# schematic.net
KiCad netlist of a schematic drawn in Altium Designer
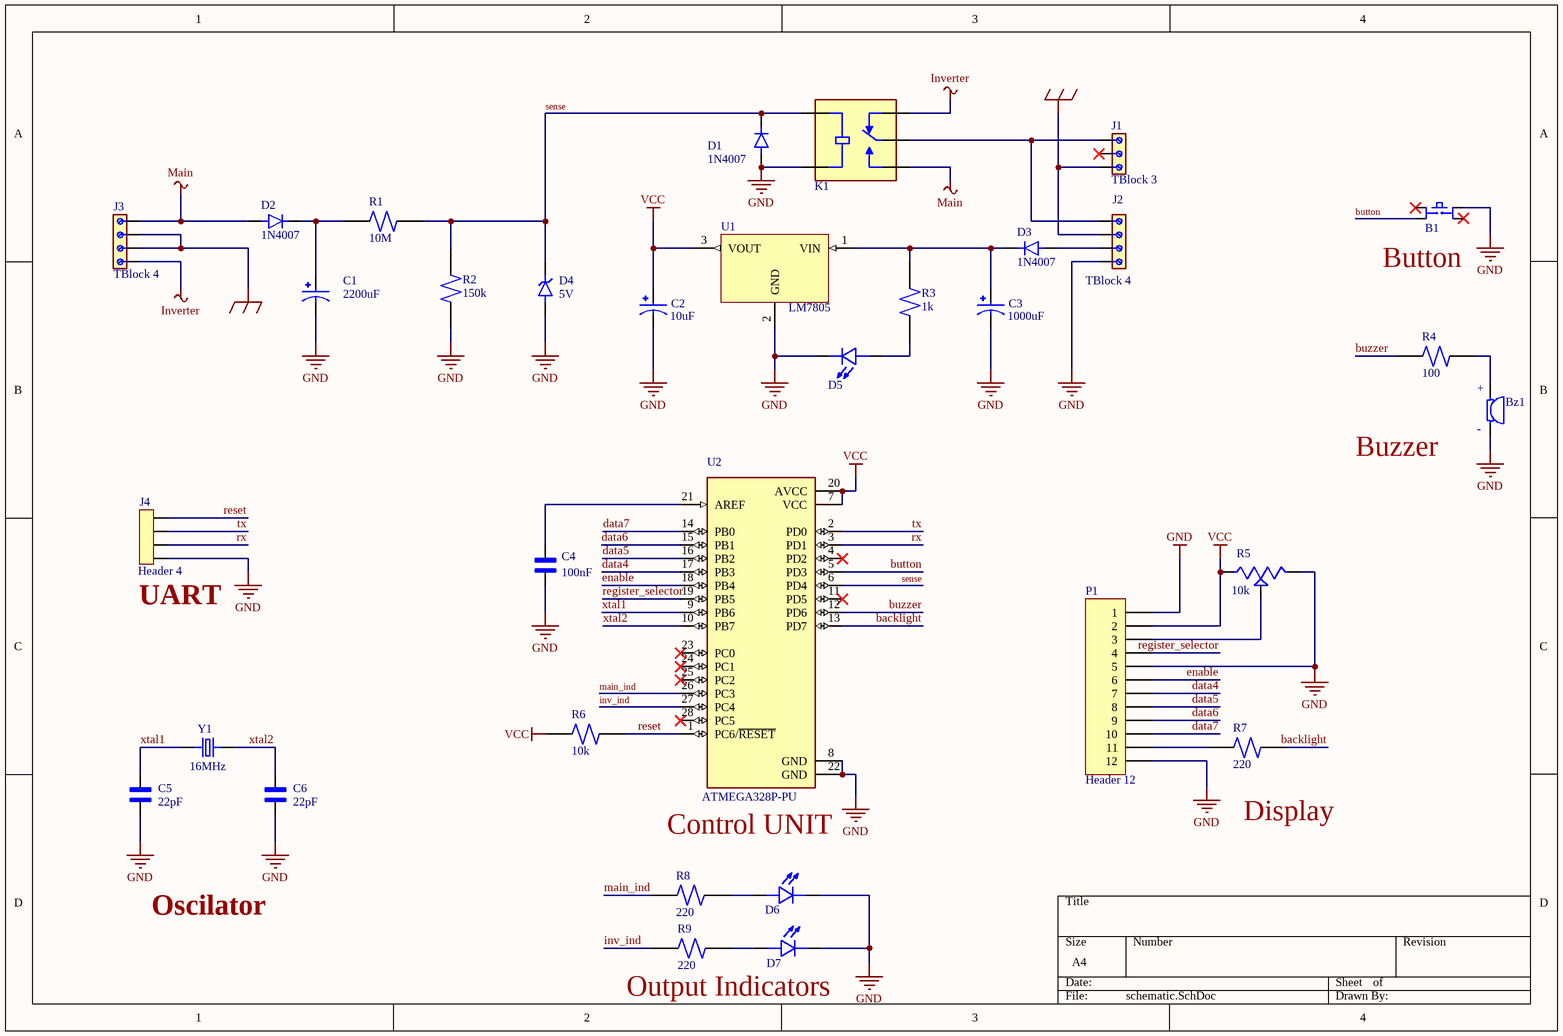
[diagram p0: schematic.SchDoc]

(export (version "E")
  (design (tool "Eeschema 10.0.6"))
  (components
    (comp (ref "B1")
      (value "Push button")
      (footprint "SW_TS02-66-95-BK-260-LCR-D")
      (libsource (lib "Installed library") (part "Push button"))
    )
    (comp (ref "Bz1")
      (value "AI-1223-TWT-12V-R")
      (footprint "XDCR_AI-1223-TWT-12V-R")
      (description "ELECTRO-MECHANICAL AUDIO INDICATOR")
      (fields (field (name "MF") "PUI Audio,"))
      (libsource (lib "Installed library") (part "Buzzer"))
    )
    (comp (ref "C1")
      (value "2200uF")
      (footprint "CAPPRD750W80D1600H2500")
      (fields (field (name "MF") "Panasonic") (field (name "MP") "ECA2GM330"))
      (libsource (lib "Installed library") (part "Capacitor (16 x 25mm)"))
    )
    (comp (ref "C2")
      (value "10uF")
      (footprint "CAPPRD500W50D500H1100")
      (description "FS-A")
      (fields (field (name "MF") "{'manufacturer': u'Panasonic'}") (field (name "MP") "EEUFS0J221B"))
      (libsource (lib "Installed library") (part "Electrolytic capacitor"))
    )
    (comp (ref "C3")
      (value "1000uF")
      (footprint "CAPPRD500W50D500H1100")
      (description "FS-A")
      (fields (field (name "MF") "{'manufacturer': u'Panasonic'}") (field (name "MP") "EEUFS0J221B"))
      (libsource (lib "Installed library") (part "Electrolytic capacitor"))
    )
    (comp (ref "C4")
      (value "100nF")
      (footprint "CAPRB500W50L450T300H550")
      (description "2200 pF Â±10% 250V Ceramic Capacitor X7R Radial")
      (fields (field (name "DIGI-KEY_PART_NUMBER") "445-173386-1-ND") (field (name "MF") "TDK"))
      (libsource (lib "Installed library") (part "Ceramic capacitor"))
    )
    (comp (ref "C5")
      (value "22pF")
      (footprint "CAPRB500W50L450T300H550")
      (description "2200 pF Â±10% 250V Ceramic Capacitor X7R Radial")
      (fields (field (name "DIGI-KEY_PART_NUMBER") "445-173386-1-ND") (field (name "MF") "TDK"))
      (libsource (lib "Installed library") (part "Ceramic capacitor"))
    )
    (comp (ref "C6")
      (value "22pF")
      (footprint "CAPRB500W50L450T300H550")
      (description "2200 pF Â±10% 250V Ceramic Capacitor X7R Radial")
      (fields (field (name "DIGI-KEY_PART_NUMBER") "445-173386-1-ND") (field (name "MF") "TDK"))
      (libsource (lib "Installed library") (part "Ceramic capacitor"))
    )
    (comp (ref "D1")
      (value "1N4007")
      (footprint "DIOAD1060W80L520D270")
      (description "Diode Switching 1KV 1A 2-Pin DO-41")
      (libsource (lib "Components") (part "1N4007"))
    )
    (comp (ref "D2")
      (value "1N4007")
      (footprint "DIOAD1060W80L520D270")
      (description "Diode Switching 1KV 1A 2-Pin DO-41")
      (libsource (lib "Components") (part "1N4007"))
    )
    (comp (ref "D3")
      (value "1N4007")
      (footprint "DIOAD1060W80L520D270")
      (description "Diode Switching 1KV 1A 2-Pin DO-41")
      (libsource (lib "Components") (part "1N4007"))
    )
    (comp (ref "D4")
      (value "5V")
      (footprint "DIOAD1060W70L435D230")
      (description "Zener Diode 16V 1W Â±5% Through Hole DO-204AL (DO-41)")
      (fields (field (name "MP") "1N4745A") (field (name "MF") "ON Semiconductor"))
      (libsource (lib "Installed library") (part "Zenner diode"))
    )
    (comp (ref "D5")
      (value "L08R5000Q1")
      (footprint "LEDRD254W57D500H1070")
      (description "LED, Orange, Through Hole, T-1 3/4 (5mm), 30 mA, 2.1 V, 635 nm")
      (fields (field (name "MF") "{'manufacturer': u'LED Technology'}"))
      (libsource (lib "Installed library") (part "LED"))
    )
    (comp (ref "D6")
      (value "L08R5000Q1")
      (footprint "LEDRD254W57D500H1070")
      (description "LED, Orange, Through Hole, T-1 3/4 (5mm), 30 mA, 2.1 V, 635 nm")
      (fields (field (name "MF") "{'manufacturer': u'LED Technology'}"))
      (libsource (lib "Installed library") (part "LED"))
    )
    (comp (ref "D7")
      (value "L08R5000Q1")
      (footprint "LEDRD254W57D500H1070")
      (description "LED, Orange, Through Hole, T-1 3/4 (5mm), 30 mA, 2.1 V, 635 nm")
      (fields (field (name "MF") "{'manufacturer': u'LED Technology'}"))
      (libsource (lib "Installed library") (part "LED"))
    )
    (comp (ref "J1")
      (value "TBlock 3")
      (footprint "Terminal block - 3Pins")
      (description "5.08 MM TERMINAL BLOCK;")
      (fields (field (name "MP") "691216510003S") (field (name "MF") "Wurth Electronics"))
      (libsource (lib "Installed library") (part "3Pins Terminal block"))
    )
    (comp (ref "J2")
      (value "TBlock 4")
      (footprint "691241510004")
      (fields (field (name "MP") "691241510004") (field (name "MF") "WÃ¼rth Elektronik"))
      (libsource (lib "Installed library") (part "Terminal block - 4Pins"))
    )
    (comp (ref "J3")
      (value "TBlock 4")
      (footprint "691241510004")
      (fields (field (name "MP") "691241510004") (field (name "MF") "WÃ¼rth Elektronik"))
      (libsource (lib "") (part "Terminal block - 4Pins_1"))
    )
    (comp (ref "J4")
      (value "Header 4")
      (footprint "SULLINS_PPTC041LFBN-RC")
      (description "4 Position Header Connector Through Hole")
      (fields (field (name "MP") "PPTC041LFBN-RC") (field (name "MF") "Sullins Connector"))
      (libsource (lib "Installed library") (part "Female header - 4Pins"))
    )
    (comp (ref "K1")
      (value "JQC-3F-1C-24VDC")
      (footprint "RELAY_JQC-3F-1C-24VDC")
      (description "Miniature PCB Relay 24VDC, 10A 250VAC, 15A 125VAC, 10A 250VAC")
      (libsource (lib "Installed library") (part "Relay (Standard)"))
    )
    (comp (ref "P1")
      (value "Header 12")
      (footprint "HDR1X12")
      (description "Header, 12-Pin")
      (fields (field (name "PUBLISHER") "Altium Limited"))
      (libsource (lib "Miscellaneous Connectors") (part "Header 12"))
    )
    (comp (ref "R1")
      (value "10M")
      (footprint "RESAD1100W55L680D260")
      (description "(MFR-25FBF52-10K) 10,2 kOhm bei 1% 0,25W, 1/4W Durchbohrlochwiderstand Axial Metal Film")
      (fields (field (name "DIGI-KEY_PART_NUMBER") "10.2KXBK-ND") (field (name "MF") "Yageo"))
      (libsource (lib "Installed library") (part "Resistor (0.25W)"))
    )
    (comp (ref "R2")
      (value "150k")
      (footprint "RESAD1100W55L680D260")
      (description "(MFR-25FBF52-10K) 10,2 kOhm bei 1% 0,25W, 1/4W Durchbohrlochwiderstand Axial Metal Film")
      (fields (field (name "DIGI-KEY_PART_NUMBER") "10.2KXBK-ND") (field (name "MF") "Yageo"))
      (libsource (lib "Installed library") (part "Resistor (0.25W)"))
    )
    (comp (ref "R3")
      (value "1k")
      (footprint "RESAD1100W55L680D260")
      (description "(MFR-25FBF52-10K) 10,2 kOhm bei 1% 0,25W, 1/4W Durchbohrlochwiderstand Axial Metal Film")
      (fields (field (name "DIGI-KEY_PART_NUMBER") "10.2KXBK-ND") (field (name "MF") "Yageo"))
      (libsource (lib "Installed library") (part "Resistor (0.25W)"))
    )
    (comp (ref "R4")
      (value "100")
      (footprint "RESAD1100W55L680D260")
      (description "(MFR-25FBF52-10K) 10,2 kOhm bei 1% 0,25W, 1/4W Durchbohrlochwiderstand Axial Metal Film")
      (fields (field (name "DIGI-KEY_PART_NUMBER") "10.2KXBK-ND") (field (name "MF") "Yageo"))
      (libsource (lib "Installed library") (part "Resistor (0.25W)"))
    )
    (comp (ref "R5")
      (value "10k")
      (footprint "TRIM_3306F-1-105")
      (fields (field (name "MF") "Bourns") (field (name "MP") "3306F-1-105"))
      (libsource (lib "Installed library") (part "Potentiometer1"))
    )
    (comp (ref "R6")
      (value "10k")
      (footprint "RESAD1100W55L680D260")
      (description "(MFR-25FBF52-10K) 10,2 kOhm bei 1% 0,25W, 1/4W Durchbohrlochwiderstand Axial Metal Film")
      (fields (field (name "DIGI-KEY_PART_NUMBER") "10.2KXBK-ND") (field (name "MF") "Yageo"))
      (libsource (lib "Installed library") (part "Resistor (0.25W)"))
    )
    (comp (ref "R7")
      (value "220")
      (footprint "RESAD1100W55L680D260")
      (description "(MFR-25FBF52-10K) 10,2 kOhm bei 1% 0,25W, 1/4W Durchbohrlochwiderstand Axial Metal Film")
      (fields (field (name "DIGI-KEY_PART_NUMBER") "10.2KXBK-ND") (field (name "MF") "Yageo"))
      (libsource (lib "Installed library") (part "Resistor (0.25W)"))
    )
    (comp (ref "R8")
      (value "220")
      (footprint "RESAD1100W55L680D260")
      (description "(MFR-25FBF52-10K) 10,2 kOhm bei 1% 0,25W, 1/4W Durchbohrlochwiderstand Axial Metal Film")
      (fields (field (name "DIGI-KEY_PART_NUMBER") "10.2KXBK-ND") (field (name "MF") "Yageo"))
      (libsource (lib "Installed library") (part "Resistor (0.25W)"))
    )
    (comp (ref "R9")
      (value "220")
      (footprint "RESAD1100W55L680D260")
      (description "(MFR-25FBF52-10K) 10,2 kOhm bei 1% 0,25W, 1/4W Durchbohrlochwiderstand Axial Metal Film")
      (fields (field (name "DIGI-KEY_PART_NUMBER") "10.2KXBK-ND") (field (name "MF") "Yageo"))
      (libsource (lib "Installed library") (part "Resistor (0.25W)"))
    )
    (comp (ref "U1")
      (value "LM7805")
      (footprint "TO255P1020X450X1968-3")
      (fields (field (name "MP") "LM7805CT/NOPB"))
      (libsource (lib "Voltage regulator") (part "LM78__"))
    )
    (comp (ref "U2")
      (value "ATMEGA328P-PU")
      (footprint "DIP794W46P254L2967H457Q28B")
      (description "ATmega Series 20 MHz 32 KB Flash 2 KB SRAM 8-Bit Microcontroller - DIP-28")
      (libsource (lib "Installed library") (part "ATMEGA328P-PU"))
    )
    (comp (ref "Y1")
      (value "16MHz")
      (footprint "XTAL_ECS-160-20-4X")
      (description "CRYSTAL T/H")
      (fields (field (name "MF") "{'manufacturer': u'ECS Inc.'}") (field (name "MP") "ECS-160-S-4"))
      (libsource (lib "Installed library") (part "Crystal oscilator"))
    )
  )
  (nets
    (net (code "1") (name "/backlight") (class "Default")
      (node (ref "R7") (pin "2") (pinfunction "2_2") (pintype "passive"))
      (node (ref "U2") (pin "13") (pinfunction "PD7_13") (pintype "bidirectional"))
    )
    (net (code "2") (name "/button") (class "Default")
      (node (ref "B1") (pin "2") (pinfunction "2_2") (pintype "passive"))
      (node (ref "U2") (pin "5") (pinfunction "PD3_5") (pintype "bidirectional"))
    )
    (net (code "3") (name "/buzzer") (class "Default")
      (node (ref "R4") (pin "1") (pinfunction "1_1") (pintype "passive"))
      (node (ref "U2") (pin "12") (pinfunction "PD6_12") (pintype "bidirectional"))
    )
    (net (code "4") (name "/data4") (class "Default")
      (node (ref "P1") (pin "7") (pinfunction "7_7") (pintype "passive"))
      (node (ref "U2") (pin "17") (pinfunction "PB3_17") (pintype "bidirectional"))
    )
    (net (code "5") (name "/data5") (class "Default")
      (node (ref "P1") (pin "8") (pinfunction "8_8") (pintype "passive"))
      (node (ref "U2") (pin "16") (pinfunction "PB2_16") (pintype "bidirectional"))
    )
    (net (code "6") (name "/data6") (class "Default")
      (node (ref "P1") (pin "9") (pinfunction "9_9") (pintype "passive"))
      (node (ref "U2") (pin "15") (pinfunction "PB1_15") (pintype "bidirectional"))
    )
    (net (code "7") (name "/data7") (class "Default")
      (node (ref "P1") (pin "10") (pinfunction "10_10") (pintype "passive"))
      (node (ref "U2") (pin "14") (pinfunction "PB0_14") (pintype "bidirectional"))
    )
    (net (code "8") (name "/enable") (class "Default")
      (node (ref "P1") (pin "6") (pinfunction "6_6") (pintype "passive"))
      (node (ref "U2") (pin "18") (pinfunction "PB4_18") (pintype "bidirectional"))
    )
    (net (code "9") (name "/inv_ind") (class "Default")
      (node (ref "R9") (pin "2") (pinfunction "2_2") (pintype "passive"))
      (node (ref "U2") (pin "27") (pinfunction "PC4_27") (pintype "bidirectional"))
    )
    (net (code "10") (name "/main_ind") (class "Default")
      (node (ref "R8") (pin "2") (pinfunction "2_2") (pintype "passive"))
      (node (ref "U2") (pin "26") (pinfunction "PC3_26") (pintype "bidirectional"))
    )
    (net (code "11") (name "/register_selector") (class "Default")
      (node (ref "P1") (pin "4") (pinfunction "4_4") (pintype "passive"))
      (node (ref "U2") (pin "19") (pinfunction "PB5_19") (pintype "bidirectional"))
    )
    (net (code "12") (name "/reset") (class "Default")
      (node (ref "J4") (pin "1") (pinfunction "1_1") (pintype "passive"))
      (node (ref "R6") (pin "1") (pinfunction "1_1") (pintype "passive"))
      (node (ref "U2") (pin "1") (pinfunction "PC6/~{RESET}_1") (pintype "bidirectional"))
    )
    (net (code "13") (name "/rx") (class "Default")
      (node (ref "J4") (pin "3") (pinfunction "3_3") (pintype "passive"))
      (node (ref "U2") (pin "3") (pinfunction "PD1_3") (pintype "bidirectional"))
    )
    (net (code "14") (name "/sense") (class "Default")
      (node (ref "D1") (pin "C") (pinfunction "C_C") (pintype "passive"))
      (node (ref "D4") (pin "C") (pinfunction "K_C") (pintype "passive"))
      (node (ref "K1") (pin "COIL1") (pinfunction "COIL1_COIL1") (pintype "passive"))
      (node (ref "R1") (pin "1") (pinfunction "1_1") (pintype "passive"))
      (node (ref "R2") (pin "1") (pinfunction "1_1") (pintype "passive"))
      (node (ref "U2") (pin "6") (pinfunction "PD4_6") (pintype "bidirectional"))
    )
    (net (code "15") (name "/tx") (class "Default")
      (node (ref "J4") (pin "2") (pinfunction "2_2") (pintype "passive"))
      (node (ref "U2") (pin "2") (pinfunction "PD0_2") (pintype "bidirectional"))
    )
    (net (code "16") (name "/xtal1") (class "Default")
      (node (ref "C5") (pin "2") (pinfunction "2_2") (pintype "passive"))
      (node (ref "U2") (pin "9") (pinfunction "PB6_9") (pintype "bidirectional"))
      (node (ref "Y1") (pin "2") (pinfunction "2_2") (pintype "passive"))
    )
    (net (code "17") (name "/xtal2") (class "Default")
      (node (ref "C6") (pin "2") (pinfunction "2_2") (pintype "passive"))
      (node (ref "U2") (pin "10") (pinfunction "PB7_10") (pintype "bidirectional"))
      (node (ref "Y1") (pin "1") (pinfunction "1_1") (pintype "passive"))
    )
    (net (code "18") (name "AGND") (class "Default")
      (node (ref "J1") (pin "3") (pinfunction "3_3") (pintype "passive"))
      (node (ref "J2") (pin "2") (pinfunction "2_2") (pintype "passive"))
      (node (ref "J3") (pin "2") (pinfunction "2_2") (pintype "passive"))
      (node (ref "J3") (pin "3") (pinfunction "3_3") (pintype "passive"))
    )
    (net (code "19") (name "GND") (class "Default")
      (node (ref "B1") (pin "3") (pinfunction "3_3") (pintype "passive"))
      (node (ref "Bz1") (pin "N") (pinfunction "NEG_N") (pintype "passive"))
      (node (ref "C1") (pin "N") (pinfunction "N_N") (pintype "passive"))
      (node (ref "C2") (pin "N") (pinfunction "N_N") (pintype "passive"))
      (node (ref "C3") (pin "N") (pinfunction "N_N") (pintype "passive"))
      (node (ref "C4") (pin "1") (pinfunction "1_1") (pintype "passive"))
      (node (ref "C5") (pin "1") (pinfunction "1_1") (pintype "passive"))
      (node (ref "C6") (pin "1") (pinfunction "1_1") (pintype "passive"))
      (node (ref "D1") (pin "A") (pinfunction "A_A") (pintype "passive"))
      (node (ref "D4") (pin "A") (pinfunction "A_A") (pintype "passive"))
      (node (ref "D5") (pin "C") (pinfunction "C_C") (pintype "passive"))
      (node (ref "D6") (pin "C") (pinfunction "C_C") (pintype "passive"))
      (node (ref "D7") (pin "C") (pinfunction "C_C") (pintype "passive"))
      (node (ref "J2") (pin "4") (pinfunction "4_4") (pintype "passive"))
      (node (ref "J4") (pin "4") (pinfunction "4_4") (pintype "passive"))
      (node (ref "K1") (pin "COIL2") (pinfunction "COIL2_COIL2") (pintype "passive"))
      (node (ref "P1") (pin "1") (pinfunction "1_1") (pintype "passive"))
      (node (ref "P1") (pin "12") (pinfunction "12_12") (pintype "passive"))
      (node (ref "P1") (pin "5") (pinfunction "5_5") (pintype "passive"))
      (node (ref "R2") (pin "2") (pinfunction "2_2") (pintype "passive"))
      (node (ref "R5") (pin "3") (pinfunction "CW_3") (pintype "passive"))
      (node (ref "U1") (pin "2") (pinfunction "GND_2") (pintype "passive"))
      (node (ref "U2") (pin "22") (pinfunction "GND_22") (pintype "power_in"))
      (node (ref "U2") (pin "8") (pinfunction "GND_8") (pintype "power_in"))
    )
    (net (code "20") (name "Inverter") (class "Default")
      (node (ref "J3") (pin "4") (pinfunction "4_4") (pintype "passive"))
      (node (ref "K1") (pin "NC") (pinfunction "NC_NC") (pintype "passive"))
    )
    (net (code "21") (name "Main") (class "Default")
      (node (ref "D2") (pin "A") (pinfunction "A_A") (pintype "passive"))
      (node (ref "J3") (pin "1") (pinfunction "1_1") (pintype "passive"))
      (node (ref "K1") (pin "NO") (pinfunction "NO_NO") (pintype "passive"))
    )
    (net (code "22") (name "Net-(Bz1-POS)") (class "Default")
      (node (ref "Bz1") (pin "P") (pinfunction "POS_P") (pintype "passive"))
      (node (ref "R4") (pin "2") (pinfunction "2_2") (pintype "passive"))
    )
    (net (code "23") (name "Net-(C1-PadP)") (class "Default")
      (node (ref "C1") (pin "P") (pinfunction "P_P") (pintype "passive"))
      (node (ref "D2") (pin "C") (pinfunction "C_C") (pintype "passive"))
      (node (ref "R1") (pin "2") (pinfunction "2_2") (pintype "passive"))
    )
    (net (code "24") (name "Net-(D3-PadA)") (class "Default")
      (node (ref "D3") (pin "A") (pinfunction "A_A") (pintype "passive"))
      (node (ref "J2") (pin "3") (pinfunction "3_3") (pintype "passive"))
    )
    (net (code "25") (name "Net-(D5-PadA)") (class "Default")
      (node (ref "D5") (pin "A") (pinfunction "A_A") (pintype "passive"))
      (node (ref "R3") (pin "1") (pinfunction "1_1") (pintype "passive"))
    )
    (net (code "26") (name "Net-(D6-PadA)") (class "Default")
      (node (ref "D6") (pin "A") (pinfunction "A_A") (pintype "passive"))
      (node (ref "R8") (pin "1") (pinfunction "1_1") (pintype "passive"))
    )
    (net (code "27") (name "Net-(D7-PadA)") (class "Default")
      (node (ref "D7") (pin "A") (pinfunction "A_A") (pintype "passive"))
      (node (ref "R9") (pin "1") (pinfunction "1_1") (pintype "passive"))
    )
    (net (code "28") (name "Net-(J1-Pad1)") (class "Default")
      (node (ref "J1") (pin "1") (pinfunction "1_1") (pintype "passive"))
      (node (ref "J2") (pin "1") (pinfunction "1_1") (pintype "passive"))
      (node (ref "K1") (pin "COM") (pinfunction "COM_COM") (pintype "passive"))
    )
    (net (code "29") (name "Net-(P1-Pad11)") (class "Default")
      (node (ref "P1") (pin "11") (pinfunction "11_11") (pintype "passive"))
      (node (ref "R7") (pin "1") (pinfunction "1_1") (pintype "passive"))
    )
    (net (code "30") (name "Net-(R5-WIPER)") (class "Default")
      (node (ref "P1") (pin "3") (pinfunction "3_3") (pintype "passive"))
      (node (ref "R5") (pin "2") (pinfunction "WIPER_2") (pintype "passive"))
    )
    (net (code "31") (name "Net-(U1-VIN)") (class "Default")
      (node (ref "C3") (pin "P") (pinfunction "P_P") (pintype "passive"))
      (node (ref "D3") (pin "C") (pinfunction "C_C") (pintype "passive"))
      (node (ref "R3") (pin "2") (pinfunction "2_2") (pintype "passive"))
      (node (ref "U1") (pin "1") (pinfunction "VIN_1") (pintype "input"))
    )
    (net (code "32") (name "Net-(U2-AREF)") (class "Default")
      (node (ref "C4") (pin "2") (pinfunction "2_2") (pintype "passive"))
      (node (ref "U2") (pin "21") (pinfunction "AREF_21") (pintype "input"))
    )
    (net (code "33") (name "VCC") (class "Default")
      (node (ref "C2") (pin "P") (pinfunction "P_P") (pintype "passive"))
      (node (ref "P1") (pin "2") (pinfunction "2_2") (pintype "passive"))
      (node (ref "R5") (pin "1") (pinfunction "CCW_1") (pintype "passive"))
      (node (ref "R6") (pin "2") (pinfunction "2_2") (pintype "passive"))
      (node (ref "U1") (pin "3") (pinfunction "VOUT_3") (pintype "output"))
      (node (ref "U2") (pin "20") (pinfunction "AVCC_20") (pintype "power_in"))
      (node (ref "U2") (pin "7") (pinfunction "VCC_7") (pintype "power_in"))
    )
    (net (code "34") (name "unconnected-(B1-Pad1)") (class "Default")
      (node (ref "B1") (pin "1") (pinfunction "1_1") (pintype "passive+no_connect"))
    )
    (net (code "35") (name "unconnected-(B1-Pad4)") (class "Default")
      (node (ref "B1") (pin "4") (pinfunction "4_4") (pintype "passive+no_connect"))
    )
    (net (code "36") (name "unconnected-(J1-Pad2)") (class "Default")
      (node (ref "J1") (pin "2") (pinfunction "2_2") (pintype "passive+no_connect"))
    )
    (net (code "37") (name "unconnected-(U2-PC0-Pad23)") (class "Default")
      (node (ref "U2") (pin "23") (pinfunction "PC0_23") (pintype "bidirectional+no_connect"))
    )
    (net (code "38") (name "unconnected-(U2-PC1-Pad24)") (class "Default")
      (node (ref "U2") (pin "24") (pinfunction "PC1_24") (pintype "bidirectional+no_connect"))
    )
    (net (code "39") (name "unconnected-(U2-PC2-Pad25)") (class "Default")
      (node (ref "U2") (pin "25") (pinfunction "PC2_25") (pintype "bidirectional+no_connect"))
    )
    (net (code "40") (name "unconnected-(U2-PC5-Pad28)") (class "Default")
      (node (ref "U2") (pin "28") (pinfunction "PC5_28") (pintype "bidirectional+no_connect"))
    )
    (net (code "41") (name "unconnected-(U2-PD2-Pad4)") (class "Default")
      (node (ref "U2") (pin "4") (pinfunction "PD2_4") (pintype "bidirectional+no_connect"))
    )
    (net (code "42") (name "unconnected-(U2-PD5-Pad11)") (class "Default")
      (node (ref "U2") (pin "11") (pinfunction "PD5_11") (pintype "bidirectional+no_connect"))
    )
  )
)
